# i2c_dev_blk.net
KiCad netlist of a schematic drawn in Altium Designer
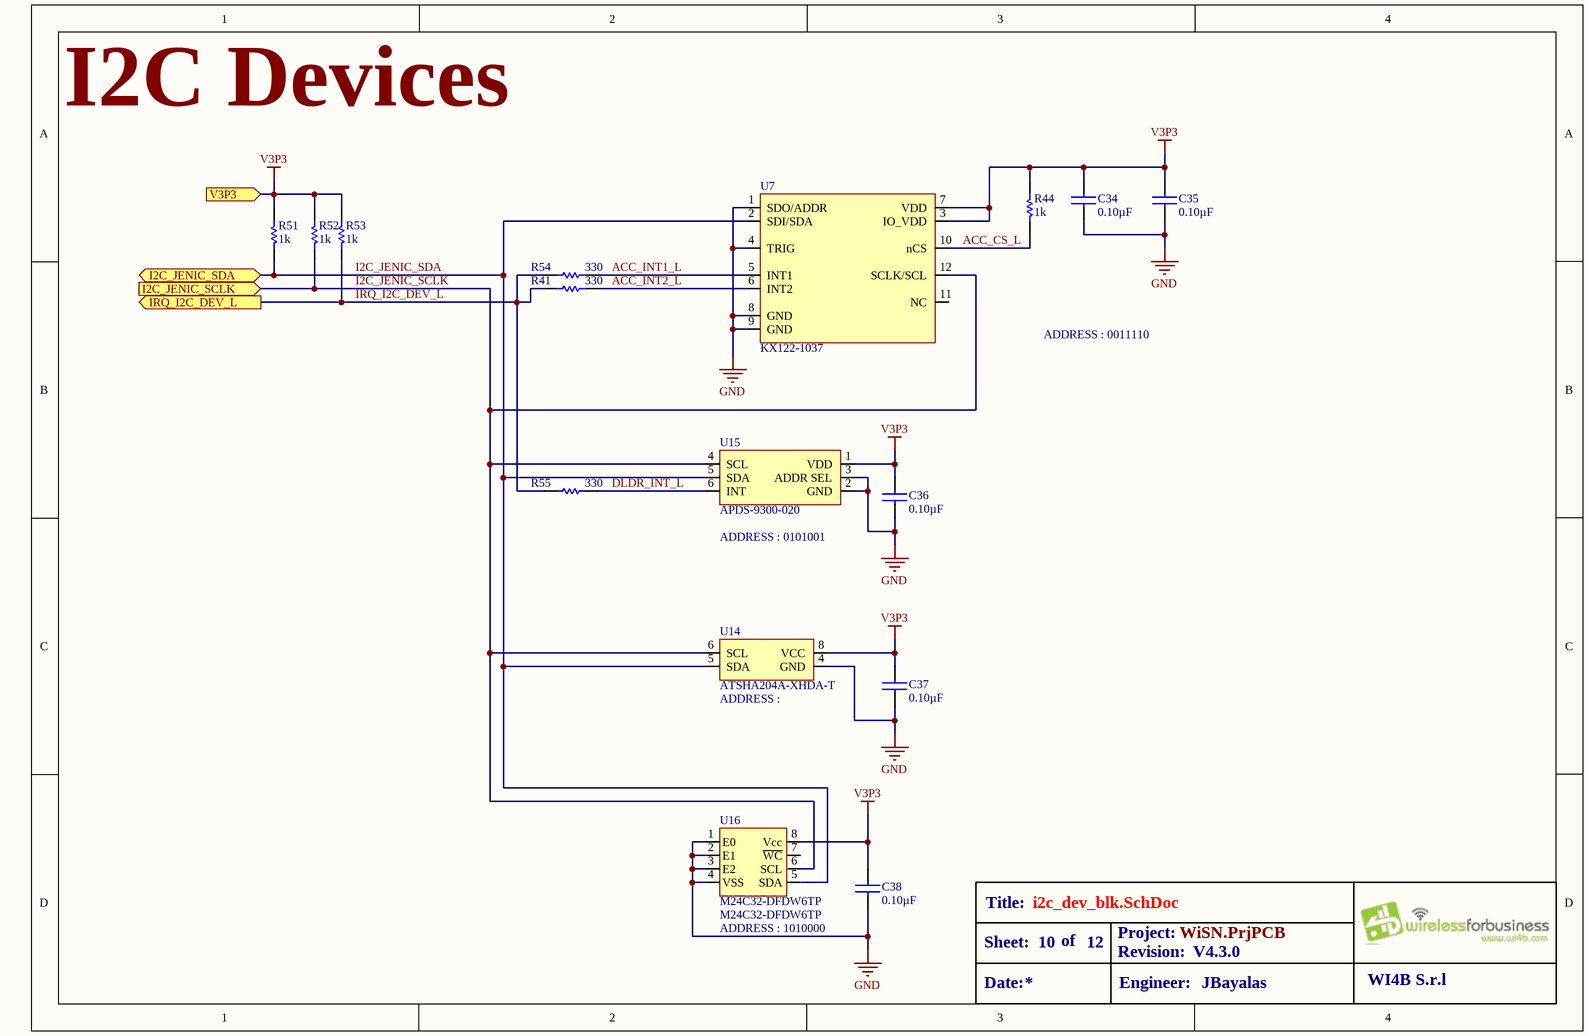
[diagram p0: i2c_dev_blk.SchDoc]

(export (version "E")
  (design (tool "Eeschema 10.0.6"))
  (components
    (comp (ref "C34")
      (value "0.10µF")
      (footprint "C0402")
      (description "CAP CER 0.1UF 50V X7R 0402")
      (fields (field (name "MPN") "GRM155R71H104ME14D"))
      (libsource (lib "Capacitor") (part "GRM155R71H104ME14D"))
    )
    (comp (ref "C35")
      (value "0.10µF")
      (footprint "C0402")
      (description "CAP CER 0.1UF 50V X7R 0402")
      (fields (field (name "MPN") "GRM155R71H104ME14D"))
      (libsource (lib "Capacitor") (part "GRM155R71H104ME14D"))
    )
    (comp (ref "C36")
      (value "0.10µF")
      (footprint "C0402")
      (description "CAP CER 0.1UF 50V X7R 0402")
      (fields (field (name "MPN") "GRM155R71H104ME14D"))
      (libsource (lib "Capacitor") (part "GRM155R71H104ME14D"))
    )
    (comp (ref "C37")
      (value "0.10µF")
      (footprint "C0402")
      (description "CAP CER 0.1UF 50V X7R 0402")
      (fields (field (name "MPN") "GRM155R71H104ME14D"))
      (libsource (lib "Capacitor") (part "GRM155R71H104ME14D"))
    )
    (comp (ref "C38")
      (value "0.10µF")
      (footprint "C0402")
      (description "CAP CER 0.1UF 50V X7R 0402")
      (fields (field (name "MPN") "GRM155R71H104ME14D"))
      (libsource (lib "Capacitor") (part "GRM155R71H104ME14D"))
    )
    (comp (ref "R41")
      (value "330")
      (footprint "R0402")
      (description "RES SMD 330 OHM 1% 1/16W 0402")
      (fields (field (name "MPN") "CRCW0402330RFKED"))
      (libsource (lib "Res") (part "CRCW0402330RFKED"))
    )
    (comp (ref "R44")
      (value "1k")
      (footprint "R0402")
      (description "RES SMD 1K OHM 1% 1/10W 0402")
      (fields (field (name "MPN") "MCS04020C1001FE000"))
      (libsource (lib "Res") (part "MCS04020C1001FE000"))
    )
    (comp (ref "R51")
      (value "1k")
      (footprint "R0402")
      (description "RES SMD 1K OHM 1% 1/10W 0402")
      (fields (field (name "MPN") "MCS04020C1001FE000"))
      (libsource (lib "Res") (part "MCS04020C1001FE000"))
    )
    (comp (ref "R52")
      (value "1k")
      (footprint "R0402")
      (description "RES SMD 1K OHM 1% 1/10W 0402")
      (fields (field (name "MPN") "MCS04020C1001FE000"))
      (libsource (lib "Res") (part "MCS04020C1001FE000"))
    )
    (comp (ref "R53")
      (value "1k")
      (footprint "R0402")
      (description "RES SMD 1K OHM 1% 1/10W 0402")
      (fields (field (name "MPN") "MCS04020C1001FE000"))
      (libsource (lib "Res") (part "MCS04020C1001FE000"))
    )
    (comp (ref "R54")
      (value "330")
      (footprint "R0402")
      (description "RES SMD 330 OHM 1% 1/16W 0402")
      (fields (field (name "MPN") "CRCW0402330RFKED"))
      (libsource (lib "Res") (part "CRCW0402330RFKED"))
    )
    (comp (ref "R55")
      (value "330")
      (footprint "R0402")
      (description "RES SMD 330 OHM 1% 1/16W 0402")
      (fields (field (name "MPN") "CRCW0402330RFKED"))
      (libsource (lib "Res") (part "CRCW0402330RFKED"))
    )
    (comp (ref "U7")
      (value "KX122-1037")
      (footprint "KX122-1037")
      (description "ACCELEROMETER 2-8G I2C/SPI 12LGA")
      (fields (field (name "MPN") "KX122-1037"))
      (libsource (lib "IC") (part "KX122-1037"))
    )
    (comp (ref "U14")
      (value "ATSHA204A-XHDA-T")
      (footprint "TSSOP-8 (wide Body)")
      (description "IC AUTHENTICATION CHIP 8TSSOP")
      (fields (field (name "MPN") "ATSHA204A-XHDA-T"))
      (libsource (lib "IC") (part "ATSHA204A-XHDA-T"))
    )
    (comp (ref "U15")
      (value "APDS-9300-020")
      (footprint "APDS-9300-020")
      (description "IC SENSOR AMBIENT LIGHT 6CHIPLED")
      (fields (field (name "MPN") "APDS-9300-020"))
      (libsource (lib "IC") (part "APDS-9300-020"))
    )
    (comp (ref "U16")
      (value "M24C32-DFDW6TP")
      (footprint "8-TSSOP")
      (description "IC EEPROM 32KBIT 400KHZ 8TSSOP")
      (fields (field (name "MPN") "M24C32-DFDW6TP"))
      (libsource (lib "IC") (part "M24C32-DFDW6TP"))
    )
  )
  (nets
    (net (code "1") (name "/ACC_CS_L") (class "Default")
      (node (ref "R44") (pin "1") (pinfunction "1_1") (pintype "passive"))
      (node (ref "U7") (pin "10") (pinfunction "nCS_10") (pintype "passive"))
    )
    (net (code "2") (name "/ACC_INT1_L") (class "Default")
      (node (ref "R54") (pin "1") (pinfunction "1_1") (pintype "passive"))
      (node (ref "U7") (pin "5") (pinfunction "INT1_5") (pintype "passive"))
    )
    (net (code "3") (name "/ACC_INT2_L") (class "Default")
      (node (ref "R41") (pin "1") (pinfunction "1_1") (pintype "passive"))
      (node (ref "U7") (pin "6") (pinfunction "INT2_6") (pintype "passive"))
    )
    (net (code "4") (name "/DLDR_INT_L") (class "Default")
      (node (ref "R55") (pin "1") (pinfunction "1_1") (pintype "passive"))
      (node (ref "U15") (pin "6") (pinfunction "INT_6") (pintype "passive"))
    )
    (net (code "5") (name "/I2C_JENIC_SCLK") (class "Default")
      (node (ref "R52") (pin "1") (pinfunction "1_1") (pintype "passive"))
      (node (ref "U14") (pin "6") (pinfunction "SCL_6") (pintype "passive"))
      (node (ref "U15") (pin "4") (pinfunction "SCL_4") (pintype "passive"))
      (node (ref "U16") (pin "6") (pinfunction "SCL_6") (pintype "passive"))
      (node (ref "U7") (pin "12") (pinfunction "SCLK/SCL_12") (pintype "passive"))
    )
    (net (code "6") (name "/I2C_JENIC_SDA") (class "Default")
      (node (ref "R51") (pin "1") (pinfunction "1_1") (pintype "passive"))
      (node (ref "U14") (pin "5") (pinfunction "SDA_5") (pintype "passive"))
      (node (ref "U15") (pin "5") (pinfunction "SDA_5") (pintype "passive"))
      (node (ref "U16") (pin "5") (pinfunction "SDA_5") (pintype "passive"))
      (node (ref "U7") (pin "2") (pinfunction "SDI/SDA_2") (pintype "passive"))
    )
    (net (code "7") (name "/IRQ_I2C_DEV_L") (class "Default")
      (node (ref "R41") (pin "2") (pinfunction "2_2") (pintype "passive"))
      (node (ref "R53") (pin "1") (pinfunction "1_1") (pintype "passive"))
      (node (ref "R54") (pin "2") (pinfunction "2_2") (pintype "passive"))
      (node (ref "R55") (pin "2") (pinfunction "2_2") (pintype "passive"))
    )
    (net (code "8") (name "GND") (class "Default")
      (node (ref "C34") (pin "2") (pinfunction "2_2") (pintype "passive"))
      (node (ref "C35") (pin "2") (pinfunction "2_2") (pintype "passive"))
      (node (ref "C36") (pin "2") (pinfunction "2_2") (pintype "passive"))
      (node (ref "C37") (pin "2") (pinfunction "2_2") (pintype "passive"))
      (node (ref "C38") (pin "2") (pinfunction "2_2") (pintype "passive"))
      (node (ref "U14") (pin "4") (pinfunction "GND_4") (pintype "passive"))
      (node (ref "U15") (pin "2") (pinfunction "GND_2") (pintype "passive"))
      (node (ref "U15") (pin "3") (pinfunction "ADDR_SEL_3") (pintype "passive"))
      (node (ref "U16") (pin "1") (pinfunction "E0_1") (pintype "passive"))
      (node (ref "U16") (pin "2") (pinfunction "E1_2") (pintype "passive"))
      (node (ref "U16") (pin "3") (pinfunction "E2_3") (pintype "passive"))
      (node (ref "U16") (pin "4") (pinfunction "VSS_4") (pintype "passive"))
      (node (ref "U7") (pin "1") (pinfunction "SDO/ADDR_1") (pintype "passive"))
      (node (ref "U7") (pin "4") (pinfunction "TRIG_4") (pintype "passive"))
      (node (ref "U7") (pin "8") (pinfunction "GND_8") (pintype "passive"))
      (node (ref "U7") (pin "9") (pinfunction "GND_9") (pintype "passive"))
    )
    (net (code "9") (name "V3P3") (class "Default")
      (node (ref "C34") (pin "1") (pinfunction "1_1") (pintype "passive"))
      (node (ref "C35") (pin "1") (pinfunction "1_1") (pintype "passive"))
      (node (ref "C36") (pin "1") (pinfunction "1_1") (pintype "passive"))
      (node (ref "C37") (pin "1") (pinfunction "1_1") (pintype "passive"))
      (node (ref "C38") (pin "1") (pinfunction "1_1") (pintype "passive"))
      (node (ref "R44") (pin "2") (pinfunction "2_2") (pintype "passive"))
      (node (ref "R51") (pin "2") (pinfunction "2_2") (pintype "passive"))
      (node (ref "R52") (pin "2") (pinfunction "2_2") (pintype "passive"))
      (node (ref "R53") (pin "2") (pinfunction "2_2") (pintype "passive"))
      (node (ref "U14") (pin "8") (pinfunction "VCC_8") (pintype "passive"))
      (node (ref "U15") (pin "1") (pinfunction "VDD_1") (pintype "passive"))
      (node (ref "U16") (pin "8") (pinfunction "Vcc_8") (pintype "passive"))
      (node (ref "U7") (pin "3") (pinfunction "IO_VDD_3") (pintype "passive"))
      (node (ref "U7") (pin "7") (pinfunction "VDD_7") (pintype "passive"))
    )
    (net (code "10") (name "unconnected-(U7-NC-Pad11)") (class "Default")
      (node (ref "U7") (pin "11") (pinfunction "NC_11") (pintype "passive"))
    )
    (net (code "11") (name "unconnected-(U16-~{WC}-Pad7)") (class "Default")
      (node (ref "U16") (pin "7") (pinfunction "~{WC}_7") (pintype "passive"))
    )
  )
)
